# SCH_LPL_ESP32signalhacker_2023-05-05.net
KiCad netlist of a schematic drawn in EasyEDA
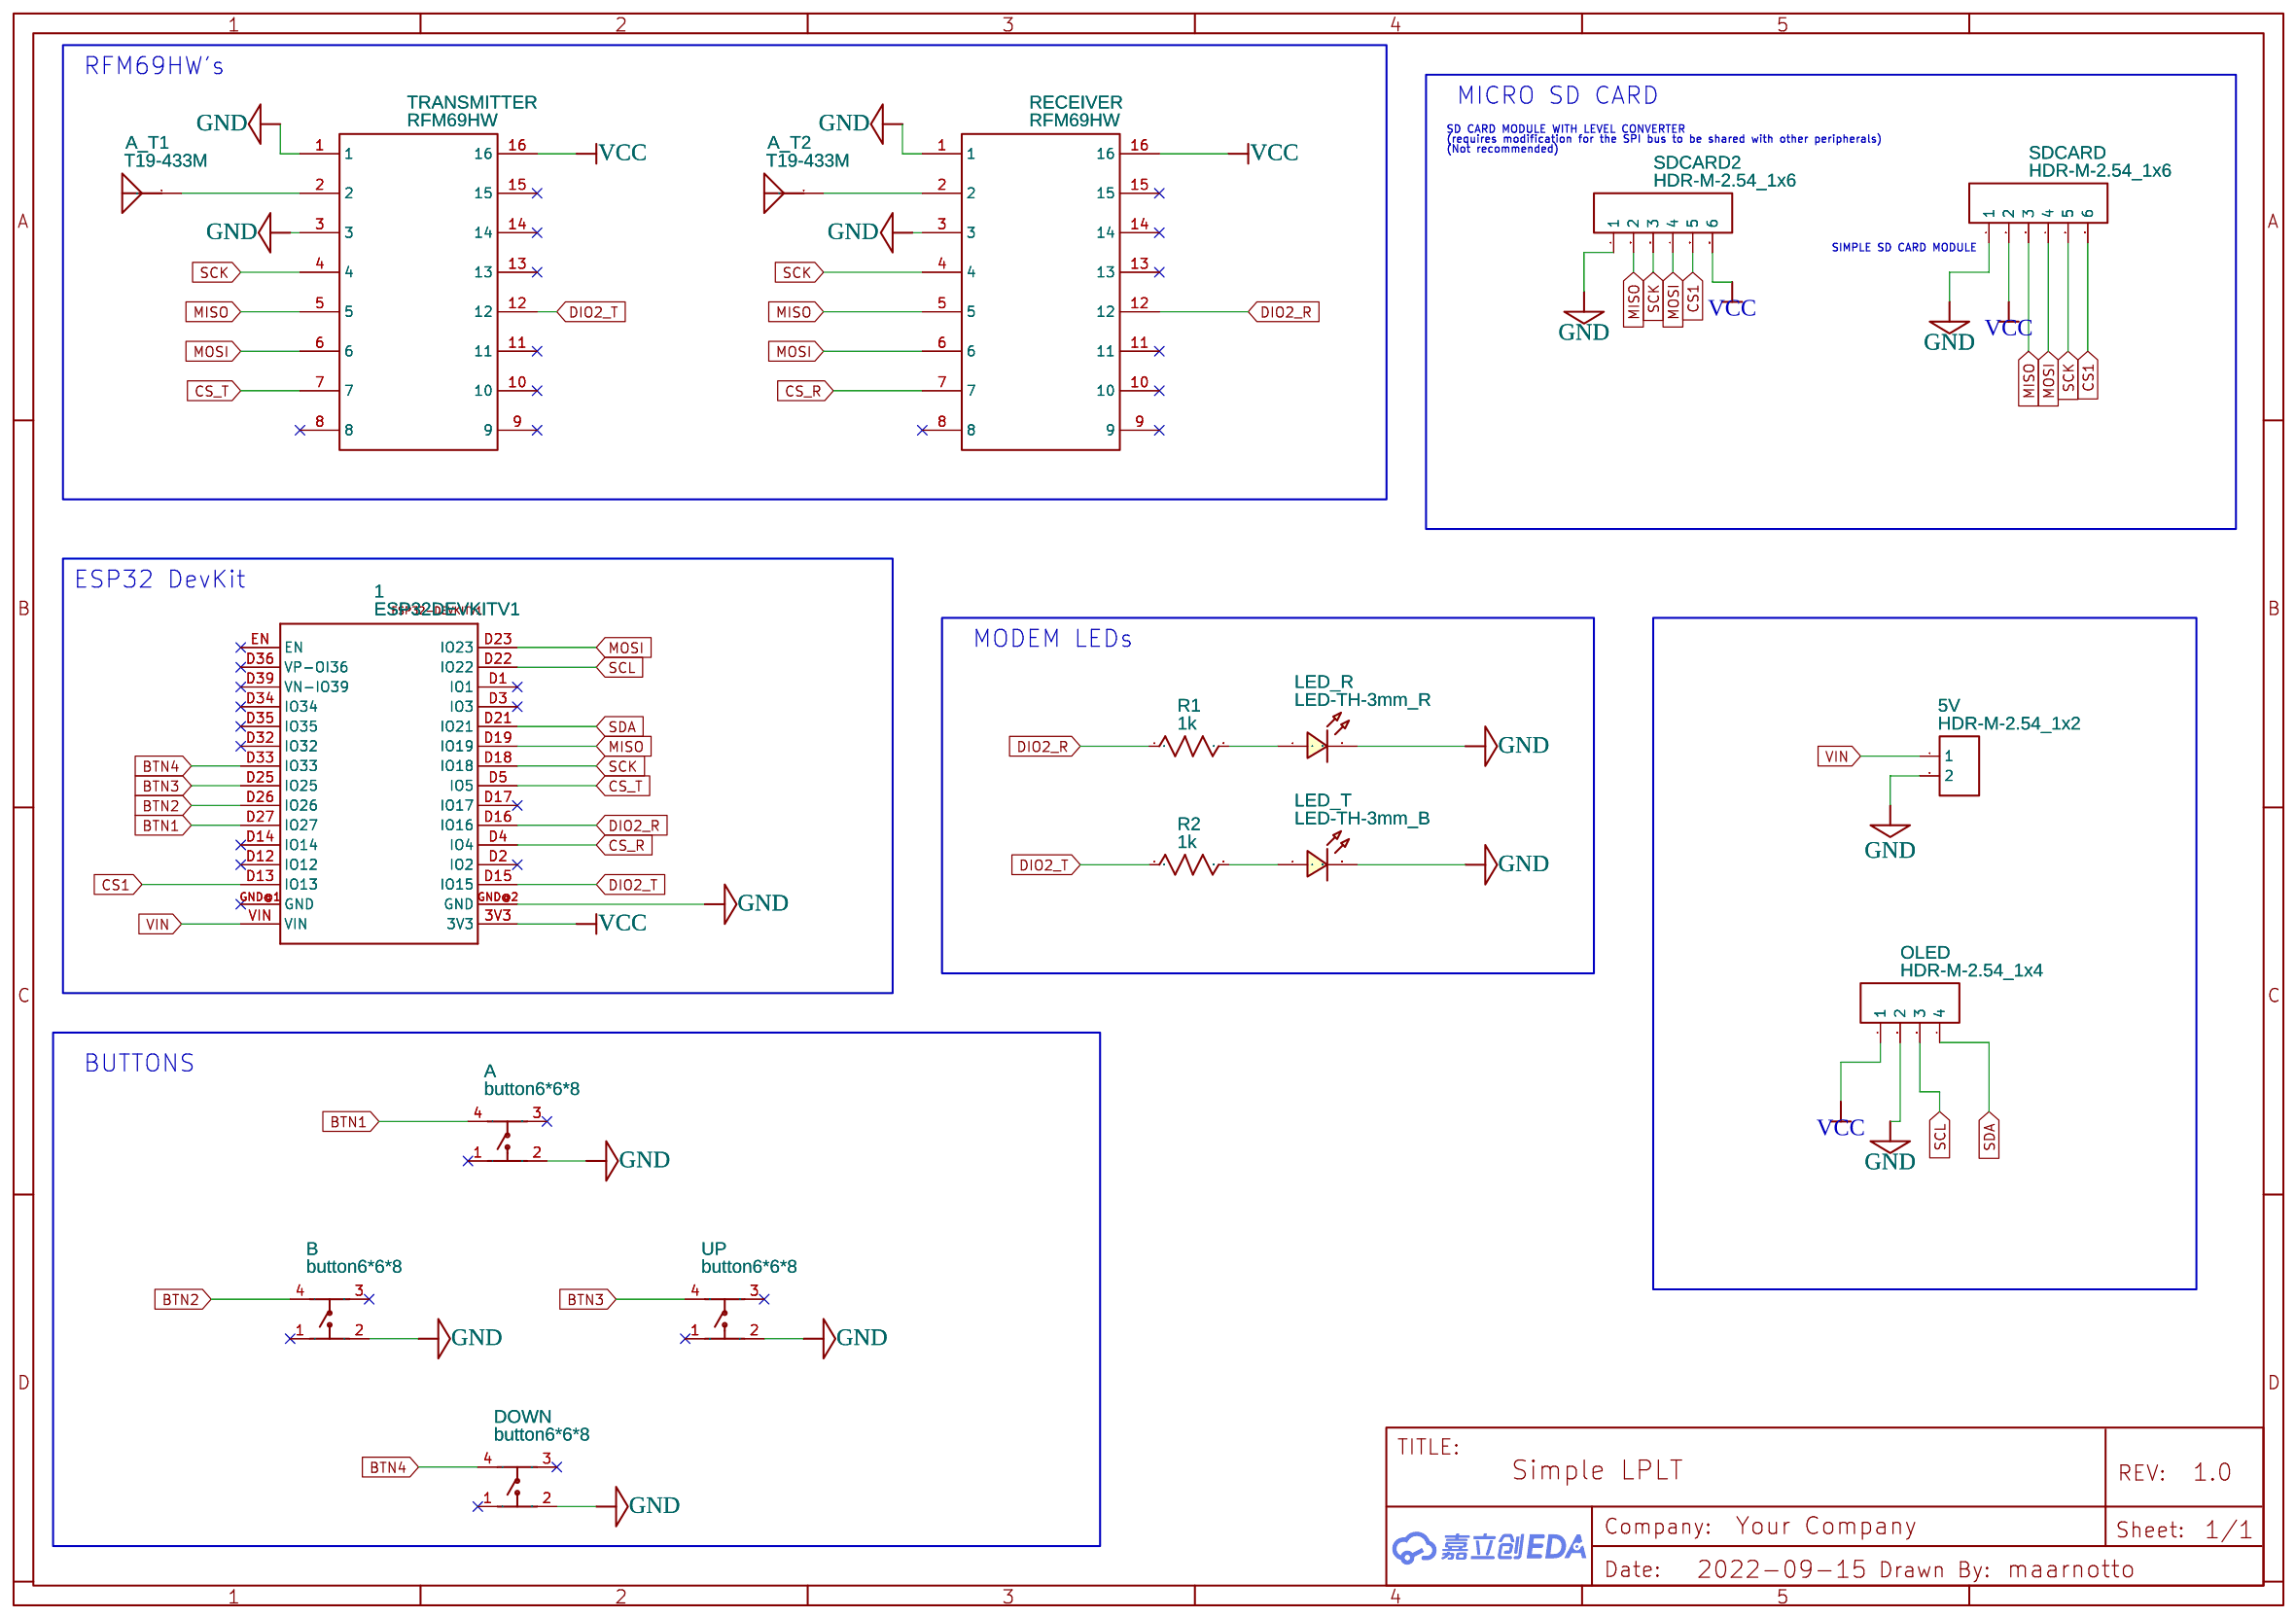
[diagram p0: schematic sheet]

(export (version "E")
  (design (tool "Eeschema 10.0.6"))
  (components
    (comp (ref "1") (value "ESP32DEVKITV1") (libsource (lib "") (part "ESP32DEVKITV1")))
    (comp (ref "5V")
      (value "HDR-M-2.54_1x2")
      (fields (field (name "BOM_Supplier Part") "C124375"))
      (libsource (lib "") (part "HDR-M-2.54_1x2"))
    )
    (comp (ref "A")
      (value "button6*6*8")
      (fields (field (name "BOM_Manufacturer Part") "?"))
      (libsource (lib "") (part "Unknown_0_-806"))
    )
    (comp (ref "A_T1")
      (value "T19-433M")
      (fields (field (name "BOM_Supplier Part") "C403733"))
      (libsource (lib "") (part "T19-433M"))
    )
    (comp (ref "A_T2")
      (value "T19-433M")
      (fields (field (name "BOM_Supplier Part") "C403733"))
      (libsource (lib "") (part "T19-433M"))
    )
    (comp (ref "B")
      (value "button6*6*8")
      (fields (field (name "BOM_Supplier Part") "C59982"))
      (libsource (lib "") (part "button6*6*8_1"))
    )
    (comp (ref "DOWN")
      (value "button6*6*8")
      (fields (field (name "BOM_Supplier Part") "C59982"))
      (libsource (lib "") (part "button6*6*8_2"))
    )
    (comp (ref "LED_R")
      (value "LED-TH-3mm_R")
      (fields
        (field (name "BOM_Manufacturer Part") "204-10SDRD/S530-A3-L")
        (field (name "BOM_Supplier Part") "C84774")
      )
      (libsource (lib "") (part "LED-TH-3mm_R"))
    )
    (comp (ref "LED_T")
      (value "LED-TH-3mm_B")
      (fields
        (field (name "BOM_Manufacturer Part") "204-10SUBC/S400-A4")
        (field (name "BOM_Supplier Part") "C86881")
      )
      (libsource (lib "") (part "LED-TH-3mm_B"))
    )
    (comp (ref "OLED")
      (value "HDR-M-2.54_1x4")
      (fields (field (name "BOM_Supplier Part") "C124378"))
      (libsource (lib "") (part "HDR-M-2.54_1x4"))
    )
    (comp (ref "R1") (value "1k") (libsource (lib "") (part "R_AXIAL-0.3_US")))
    (comp (ref "R2") (value "1k") (libsource (lib "") (part "R_AXIAL-0.3_US")))
    (comp (ref "RECEIVER") (value "RFM69HW") (libsource (lib "") (part "RFM69HW_1")))
    (comp (ref "SDCARD")
      (value "HDR-M-2.54_1x6")
      (fields (field (name "BOM_Supplier Part") "C190819"))
      (libsource (lib "") (part "HDR-M-2.54_1x6"))
    )
    (comp (ref "SDCARD2")
      (value "HDR-M-2.54_1x6")
      (fields (field (name "BOM_Supplier Part") "C190819"))
      (libsource (lib "") (part "HDR-M-2.54_1x6"))
    )
    (comp (ref "TRANSMITTER") (value "RFM69HW") (libsource (lib "") (part "RFM69HW")))
    (comp (ref "UP")
      (value "button6*6*8")
      (fields (field (name "BOM_Supplier Part") "C59982"))
      (libsource (lib "") (part "button6*6*8_3"))
    )
  )
  (nets
    (net (code "1") (name "BTN1") (class "Default")
      (node (ref "1") (pin "D27") (pinfunction "IO27_D27") (pintype "bidirectional"))
      (node (ref "A") (pin "4") (pinfunction "4_4") (pintype "unspecified"))
    )
    (net (code "2") (name "BTN2") (class "Default")
      (node (ref "1") (pin "D26") (pinfunction "IO26_D26") (pintype "bidirectional"))
      (node (ref "B") (pin "4") (pinfunction "4_4") (pintype "unspecified"))
    )
    (net (code "3") (name "BTN3") (class "Default")
      (node (ref "1") (pin "D25") (pinfunction "IO25_D25") (pintype "bidirectional"))
      (node (ref "UP") (pin "4") (pinfunction "4_4") (pintype "unspecified"))
    )
    (net (code "4") (name "BTN4") (class "Default")
      (node (ref "1") (pin "D33") (pinfunction "IO33_D33") (pintype "bidirectional"))
      (node (ref "DOWN") (pin "4") (pinfunction "4_4") (pintype "unspecified"))
    )
    (net (code "5") (name "CS1") (class "Default")
      (node (ref "1") (pin "D13") (pinfunction "IO13_D13") (pintype "bidirectional"))
      (node (ref "SDCARD") (pin "6") (pinfunction "6_6") (pintype "input"))
      (node (ref "SDCARD2") (pin "5") (pinfunction "5_5") (pintype "input"))
    )
    (net (code "6") (name "CS_R") (class "Default")
      (node (ref "1") (pin "D4") (pinfunction "IO4_D4") (pintype "bidirectional"))
      (node (ref "RECEIVER") (pin "7") (pinfunction "7_7") (pintype "unspecified"))
    )
    (net (code "7") (name "CS_T") (class "Default")
      (node (ref "1") (pin "D5") (pinfunction "IO5_D5") (pintype "bidirectional"))
      (node (ref "TRANSMITTER") (pin "7") (pinfunction "7_7") (pintype "unspecified"))
    )
    (net (code "8") (name "DIO2_R") (class "Default")
      (node (ref "1") (pin "D16") (pinfunction "IO16_D16") (pintype "bidirectional"))
      (node (ref "R1") (pin "1") (pinfunction "1_1") (pintype "unspecified"))
      (node (ref "RECEIVER") (pin "12") (pinfunction "12_12") (pintype "unspecified"))
    )
    (net (code "9") (name "DIO2_T") (class "Default")
      (node (ref "1") (pin "D15") (pinfunction "IO15_D15") (pintype "bidirectional"))
      (node (ref "R2") (pin "1") (pinfunction "1_1") (pintype "unspecified"))
      (node (ref "TRANSMITTER") (pin "12") (pinfunction "12_12") (pintype "unspecified"))
    )
    (net (code "10") (name "GND") (class "Default")
      (node (ref "1") (pin "GND@2") (pinfunction "GND_GND@2") (pintype "bidirectional"))
      (node (ref "5V") (pin "2") (pinfunction "2_2") (pintype "unspecified"))
      (node (ref "A") (pin "2") (pinfunction "2_2") (pintype "unspecified"))
      (node (ref "B") (pin "2") (pinfunction "2_2") (pintype "unspecified"))
      (node (ref "DOWN") (pin "2") (pinfunction "2_2") (pintype "unspecified"))
      (node (ref "LED_R") (pin "2") (pinfunction "2_2") (pintype "unspecified"))
      (node (ref "LED_T") (pin "2") (pinfunction "2_2") (pintype "unspecified"))
      (node (ref "OLED") (pin "2") (pinfunction "2_2") (pintype "unspecified"))
      (node (ref "RECEIVER") (pin "1") (pinfunction "1_1") (pintype "unspecified"))
      (node (ref "RECEIVER") (pin "3") (pinfunction "3_3") (pintype "unspecified"))
      (node (ref "SDCARD") (pin "1") (pinfunction "1_1") (pintype "input"))
      (node (ref "SDCARD2") (pin "1") (pinfunction "1_1") (pintype "input"))
      (node (ref "TRANSMITTER") (pin "1") (pinfunction "1_1") (pintype "unspecified"))
      (node (ref "TRANSMITTER") (pin "3") (pinfunction "3_3") (pintype "unspecified"))
      (node (ref "UP") (pin "2") (pinfunction "2_2") (pintype "unspecified"))
    )
    (net (code "11") (name "MISO") (class "Default")
      (node (ref "1") (pin "D19") (pinfunction "IO19_D19") (pintype "bidirectional"))
      (node (ref "RECEIVER") (pin "5") (pinfunction "5_5") (pintype "unspecified"))
      (node (ref "SDCARD") (pin "3") (pinfunction "3_3") (pintype "input"))
      (node (ref "SDCARD2") (pin "2") (pinfunction "2_2") (pintype "input"))
      (node (ref "TRANSMITTER") (pin "5") (pinfunction "5_5") (pintype "unspecified"))
    )
    (net (code "12") (name "MOSI") (class "Default")
      (node (ref "1") (pin "D23") (pinfunction "IO23_D23") (pintype "bidirectional"))
      (node (ref "RECEIVER") (pin "6") (pinfunction "6_6") (pintype "unspecified"))
      (node (ref "SDCARD") (pin "4") (pinfunction "4_4") (pintype "input"))
      (node (ref "SDCARD2") (pin "4") (pinfunction "4_4") (pintype "input"))
      (node (ref "TRANSMITTER") (pin "6") (pinfunction "6_6") (pintype "unspecified"))
    )
    (net (code "13") (name "Net-(A_T1-Pad1)") (class "Default")
      (node (ref "A_T1") (pin "1") (pinfunction "1_1") (pintype "unspecified"))
      (node (ref "TRANSMITTER") (pin "2") (pinfunction "2_2") (pintype "unspecified"))
    )
    (net (code "14") (name "Net-(A_T2-Pad1)") (class "Default")
      (node (ref "A_T2") (pin "1") (pinfunction "1_1") (pintype "unspecified"))
      (node (ref "RECEIVER") (pin "2") (pinfunction "2_2") (pintype "unspecified"))
    )
    (net (code "15") (name "Net-(LED_R-Pad1)") (class "Default")
      (node (ref "LED_R") (pin "1") (pinfunction "1_1") (pintype "unspecified"))
      (node (ref "R1") (pin "2") (pinfunction "2_2") (pintype "unspecified"))
    )
    (net (code "16") (name "Net-(LED_T-Pad1)") (class "Default")
      (node (ref "LED_T") (pin "1") (pinfunction "1_1") (pintype "unspecified"))
      (node (ref "R2") (pin "2") (pinfunction "2_2") (pintype "unspecified"))
    )
    (net (code "17") (name "SCK") (class "Default")
      (node (ref "1") (pin "D18") (pinfunction "IO18_D18") (pintype "bidirectional"))
      (node (ref "RECEIVER") (pin "4") (pinfunction "4_4") (pintype "unspecified"))
      (node (ref "SDCARD") (pin "5") (pinfunction "5_5") (pintype "input"))
      (node (ref "SDCARD2") (pin "3") (pinfunction "3_3") (pintype "input"))
      (node (ref "TRANSMITTER") (pin "4") (pinfunction "4_4") (pintype "unspecified"))
    )
    (net (code "18") (name "SCL") (class "Default")
      (node (ref "1") (pin "D22") (pinfunction "IO22_D22") (pintype "bidirectional"))
      (node (ref "OLED") (pin "3") (pinfunction "3_3") (pintype "unspecified"))
    )
    (net (code "19") (name "SDA") (class "Default")
      (node (ref "1") (pin "D21") (pinfunction "IO21_D21") (pintype "bidirectional"))
      (node (ref "OLED") (pin "4") (pinfunction "4_4") (pintype "unspecified"))
    )
    (net (code "20") (name "VCC") (class "Default")
      (node (ref "1") (pin "3V3") (pinfunction "3V3_3V3") (pintype "bidirectional"))
      (node (ref "OLED") (pin "1") (pinfunction "1_1") (pintype "unspecified"))
      (node (ref "RECEIVER") (pin "16") (pinfunction "16_16") (pintype "unspecified"))
      (node (ref "SDCARD") (pin "2") (pinfunction "2_2") (pintype "input"))
      (node (ref "SDCARD2") (pin "6") (pinfunction "6_6") (pintype "input"))
      (node (ref "TRANSMITTER") (pin "16") (pinfunction "16_16") (pintype "unspecified"))
    )
    (net (code "21") (name "VIN") (class "Default")
      (node (ref "1") (pin "VIN") (pinfunction "VIN_VIN") (pintype "bidirectional"))
      (node (ref "5V") (pin "1") (pinfunction "1_1") (pintype "unspecified"))
    )
    (net (code "22") (name "unconnected-(1-GND-PadGND@1)") (class "Default")
      (node (ref "1") (pin "GND@1") (pinfunction "GND_GND@1") (pintype "bidirectional+no_connect"))
    )
    (net (code "23") (name "unconnected-(1-IO1-PadD1)") (class "Default")
      (node (ref "1") (pin "D1") (pinfunction "IO1_D1") (pintype "bidirectional+no_connect"))
    )
    (net (code "24") (name "unconnected-(1-IO2-PadD2)") (class "Default")
      (node (ref "1") (pin "D2") (pinfunction "IO2_D2") (pintype "bidirectional+no_connect"))
    )
    (net (code "25") (name "unconnected-(1-IO3-PadD3)") (class "Default")
      (node (ref "1") (pin "D3") (pinfunction "IO3_D3") (pintype "bidirectional+no_connect"))
    )
    (net (code "26") (name "unconnected-(1-IO12-PadD12)") (class "Default")
      (node (ref "1") (pin "D12") (pinfunction "IO12_D12") (pintype "bidirectional+no_connect"))
    )
    (net (code "27") (name "unconnected-(1-IO14-PadD14)") (class "Default")
      (node (ref "1") (pin "D14") (pinfunction "IO14_D14") (pintype "bidirectional+no_connect"))
    )
    (net (code "28") (name "unconnected-(1-IO17-PadD17)") (class "Default")
      (node (ref "1") (pin "D17") (pinfunction "IO17_D17") (pintype "bidirectional+no_connect"))
    )
    (net (code "29") (name "unconnected-(1-IO32-PadD32)") (class "Default")
      (node (ref "1") (pin "D32") (pinfunction "IO32_D32") (pintype "bidirectional+no_connect"))
    )
    (net (code "30") (name "unconnected-(1-IO34-PadD34)") (class "Default")
      (node (ref "1") (pin "D34") (pinfunction "IO34_D34") (pintype "bidirectional+no_connect"))
    )
    (net (code "31") (name "unconnected-(1-IO35-PadD35)") (class "Default")
      (node (ref "1") (pin "D35") (pinfunction "IO35_D35") (pintype "bidirectional+no_connect"))
    )
    (net (code "32") (name "unconnected-(1-PadEN)") (class "Default")
      (node (ref "1") (pin "EN") (pinfunction "EN_EN") (pintype "bidirectional+no_connect"))
    )
    (net (code "33") (name "unconnected-(1-VN-IO39-PadD39)") (class "Default")
      (node (ref "1") (pin "D39") (pinfunction "VN-IO39_D39") (pintype "bidirectional+no_connect"))
    )
    (net (code "34") (name "unconnected-(1-VP-OI36-PadD36)") (class "Default")
      (node (ref "1") (pin "D36") (pinfunction "VP-OI36_D36") (pintype "bidirectional+no_connect"))
    )
    (net (code "35") (name "unconnected-(A-Pad1)") (class "Default")
      (node (ref "A") (pin "1") (pinfunction "1_1") (pintype "unspecified+no_connect"))
    )
    (net (code "36") (name "unconnected-(A-Pad3)") (class "Default")
      (node (ref "A") (pin "3") (pinfunction "3_3") (pintype "unspecified+no_connect"))
    )
    (net (code "37") (name "unconnected-(B-Pad1)") (class "Default")
      (node (ref "B") (pin "1") (pinfunction "1_1") (pintype "unspecified+no_connect"))
    )
    (net (code "38") (name "unconnected-(B-Pad3)") (class "Default")
      (node (ref "B") (pin "3") (pinfunction "3_3") (pintype "unspecified+no_connect"))
    )
    (net (code "39") (name "unconnected-(DOWN-Pad1)") (class "Default")
      (node (ref "DOWN") (pin "1") (pinfunction "1_1") (pintype "unspecified+no_connect"))
    )
    (net (code "40") (name "unconnected-(DOWN-Pad3)") (class "Default")
      (node (ref "DOWN") (pin "3") (pinfunction "3_3") (pintype "unspecified+no_connect"))
    )
    (net (code "41") (name "unconnected-(RECEIVER-Pad8)") (class "Default")
      (node (ref "RECEIVER") (pin "8") (pinfunction "8_8") (pintype "unspecified+no_connect"))
    )
    (net (code "42") (name "unconnected-(RECEIVER-Pad9)") (class "Default")
      (node (ref "RECEIVER") (pin "9") (pinfunction "9_9") (pintype "unspecified+no_connect"))
    )
    (net (code "43") (name "unconnected-(RECEIVER-Pad10)") (class "Default")
      (node (ref "RECEIVER") (pin "10") (pinfunction "10_10") (pintype "unspecified+no_connect"))
    )
    (net (code "44") (name "unconnected-(RECEIVER-Pad11)") (class "Default")
      (node (ref "RECEIVER") (pin "11") (pinfunction "11_11") (pintype "unspecified+no_connect"))
    )
    (net (code "45") (name "unconnected-(RECEIVER-Pad13)") (class "Default")
      (node (ref "RECEIVER") (pin "13") (pinfunction "13_13") (pintype "unspecified+no_connect"))
    )
    (net (code "46") (name "unconnected-(RECEIVER-Pad14)") (class "Default")
      (node (ref "RECEIVER") (pin "14") (pinfunction "14_14") (pintype "unspecified+no_connect"))
    )
    (net (code "47") (name "unconnected-(RECEIVER-Pad15)") (class "Default")
      (node (ref "RECEIVER") (pin "15") (pinfunction "15_15") (pintype "unspecified+no_connect"))
    )
    (net (code "48") (name "unconnected-(TRANSMITTER-Pad8)") (class "Default")
      (node (ref "TRANSMITTER") (pin "8") (pinfunction "8_8") (pintype "unspecified+no_connect"))
    )
    (net (code "49") (name "unconnected-(TRANSMITTER-Pad9)") (class "Default")
      (node (ref "TRANSMITTER") (pin "9") (pinfunction "9_9") (pintype "unspecified+no_connect"))
    )
    (net (code "50") (name "unconnected-(TRANSMITTER-Pad10)") (class "Default")
      (node (ref "TRANSMITTER") (pin "10") (pinfunction "10_10") (pintype "unspecified+no_connect"))
    )
    (net (code "51") (name "unconnected-(TRANSMITTER-Pad11)") (class "Default")
      (node (ref "TRANSMITTER") (pin "11") (pinfunction "11_11") (pintype "unspecified+no_connect"))
    )
    (net (code "52") (name "unconnected-(TRANSMITTER-Pad13)") (class "Default")
      (node (ref "TRANSMITTER") (pin "13") (pinfunction "13_13") (pintype "unspecified+no_connect"))
    )
    (net (code "53") (name "unconnected-(TRANSMITTER-Pad14)") (class "Default")
      (node (ref "TRANSMITTER") (pin "14") (pinfunction "14_14") (pintype "unspecified+no_connect"))
    )
    (net (code "54") (name "unconnected-(TRANSMITTER-Pad15)") (class "Default")
      (node (ref "TRANSMITTER") (pin "15") (pinfunction "15_15") (pintype "unspecified+no_connect"))
    )
    (net (code "55") (name "unconnected-(UP-Pad1)") (class "Default")
      (node (ref "UP") (pin "1") (pinfunction "1_1") (pintype "unspecified+no_connect"))
    )
    (net (code "56") (name "unconnected-(UP-Pad3)") (class "Default")
      (node (ref "UP") (pin "3") (pinfunction "3_3") (pintype "unspecified+no_connect"))
    )
  )
)
